# 01_-_CPU.net
KiCad netlist of a schematic drawn in Altium Designer
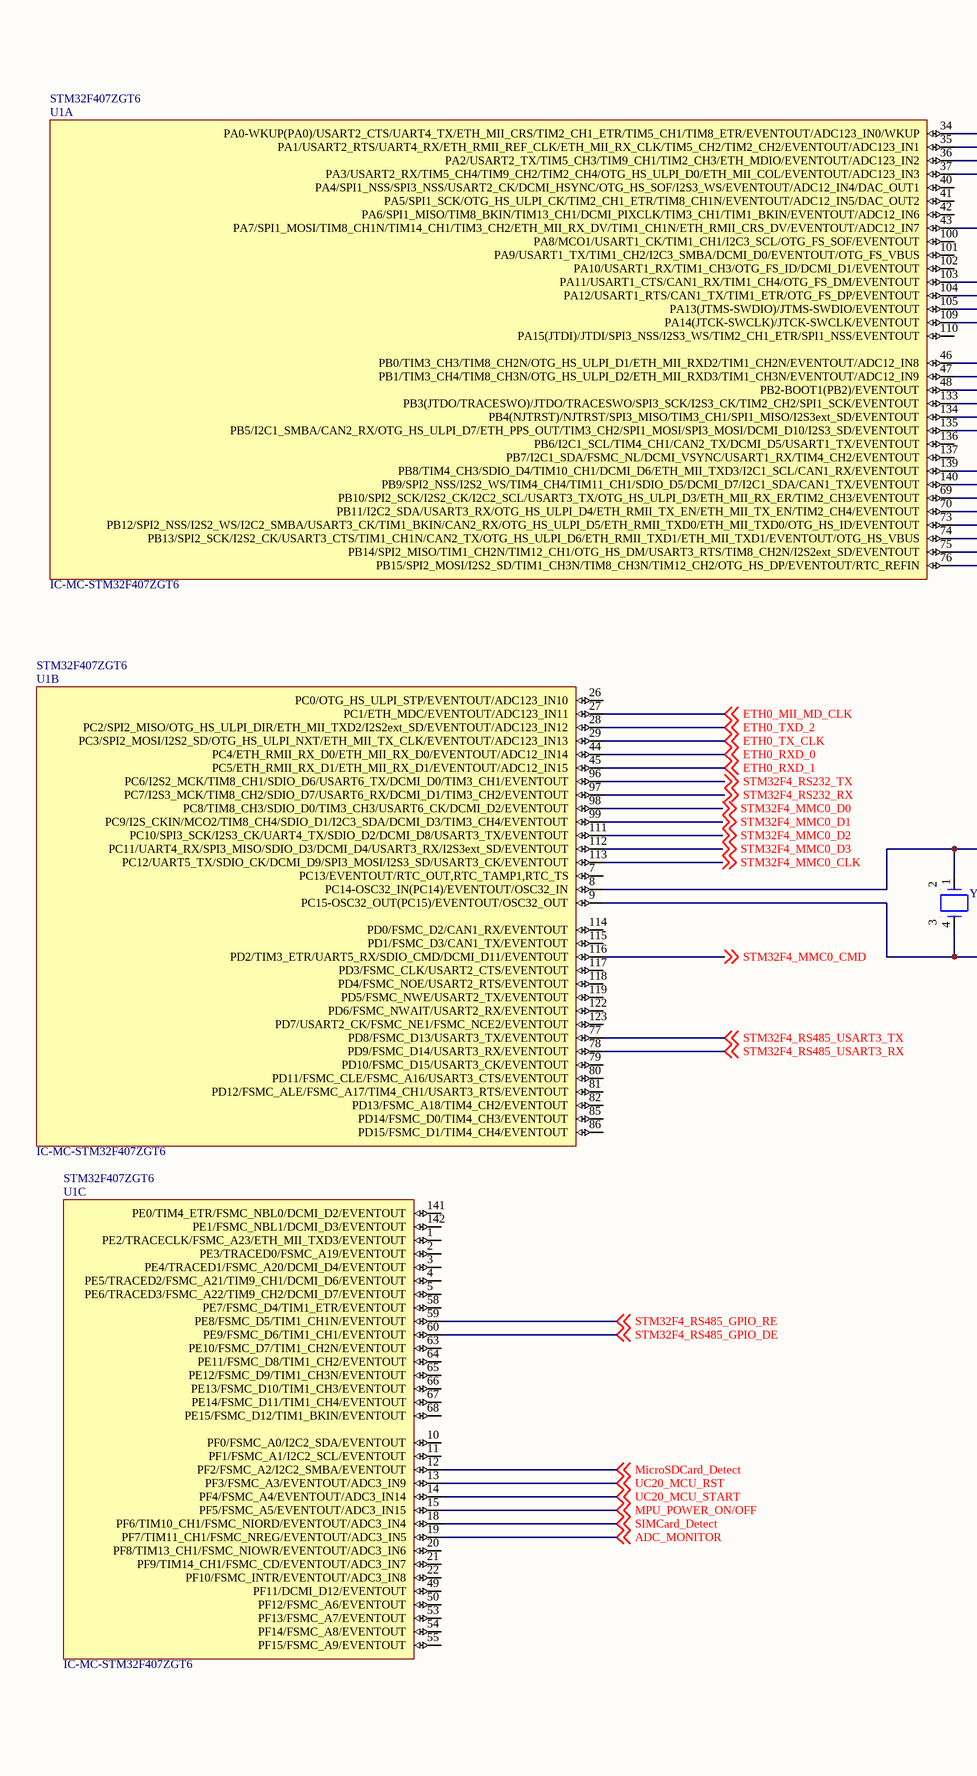
[diagram p0: [01] - CPU.SchDoc, left]
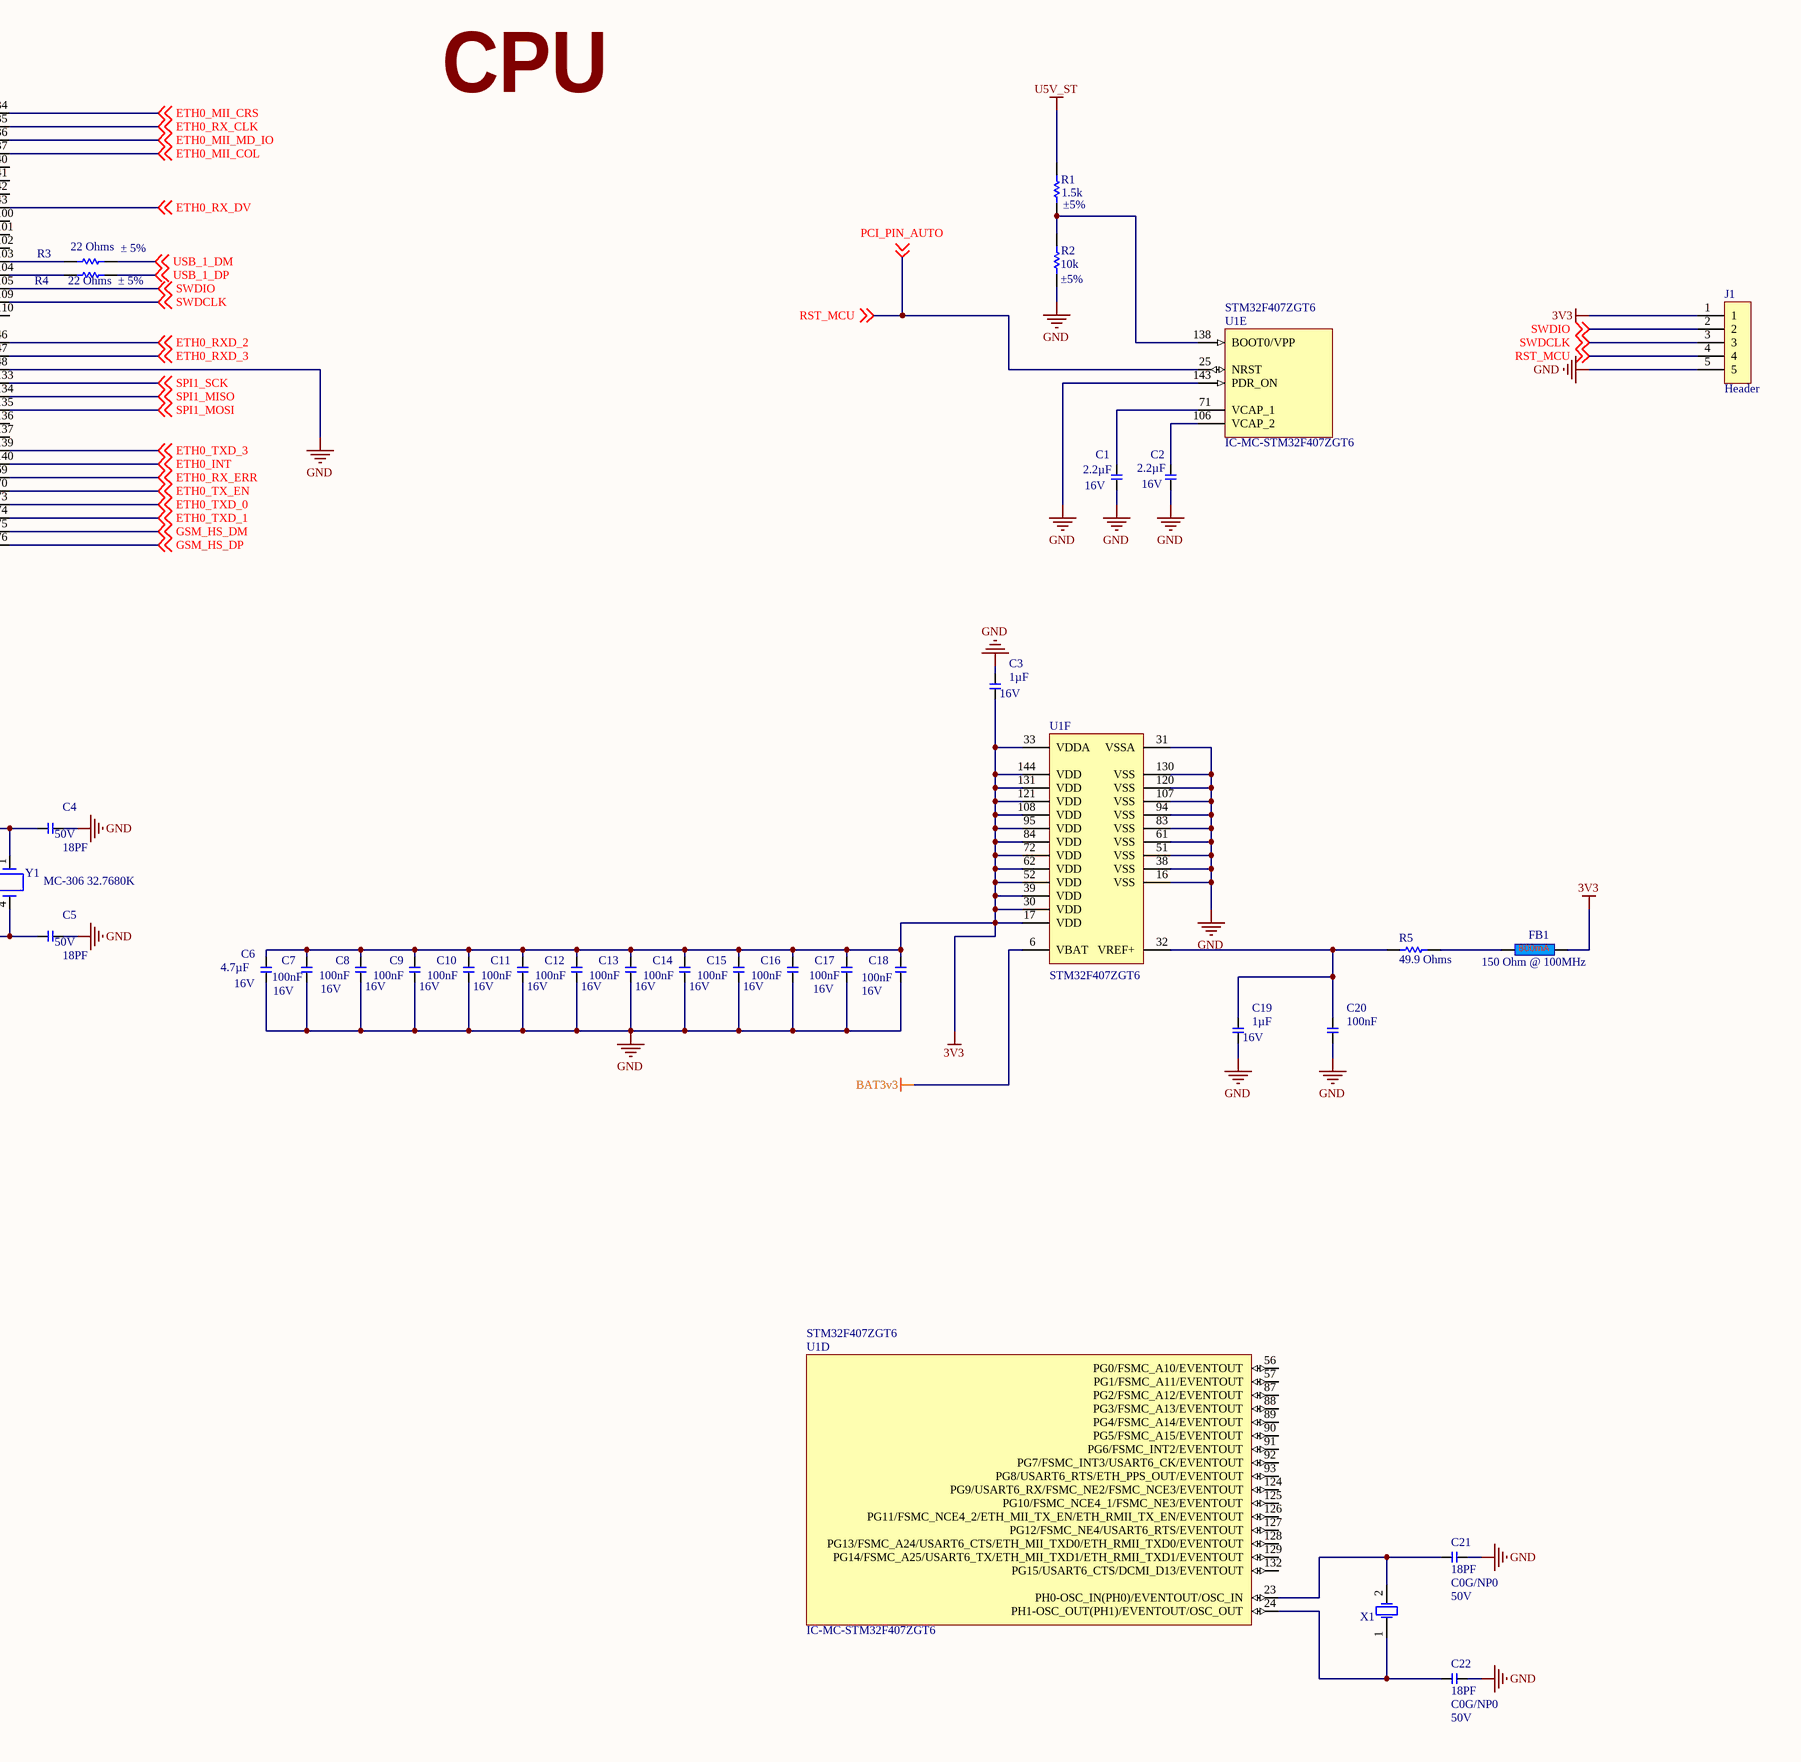
[diagram p1: [01] - CPU.SchDoc, right]

(export (version "E")
  (design (tool "Eeschema 10.0.6"))
  (components
    (comp (ref "C1")
      (value "2.2µF")
      (footprint "C0805")
      (description "KEMET - C0805C225K4RACTU - CAP, MLCC, X7R, 2.2UF, 16V, 0805")
      (fields
        (field (name "MANUFACTURER") "Kemet")
        (field (name "MANUFACTURER PART NUMBER") "C0805C225K4RACTU")
        (field (name "CAPACITANCE") "2.2µF")
        (field (name "VOLTAGE - RATED") "16V")
      )
      (libsource (lib "CPU_STM_080816") (part "C-2.2UF,16V,0805"))
    )
    (comp (ref "C2")
      (value "2.2µF")
      (footprint "C0805")
      (description "KEMET - C0805C225K4RACTU - CAP, MLCC, X7R, 2.2UF, 16V, 0805")
      (fields
        (field (name "MANUFACTURER") "Kemet")
        (field (name "MANUFACTURER PART NUMBER") "C0805C225K4RACTU")
        (field (name "CAPACITANCE") "2.2µF")
        (field (name "VOLTAGE - RATED") "16V")
      )
      (libsource (lib "CPU_STM_080816") (part "C-2.2UF,16V,0805"))
    )
    (comp (ref "C3")
      (value "1µF")
      (footprint "C0805")
      (description "AVX - 0805YC105KAT2A - CAP, MLCC, X7R, 1UF, 16V, 0805")
      (fields
        (field (name "MANUFACTURER") "AVX Corporation")
        (field (name "MANUFACTURER PART NUMBER") "0805YC105KAT2A")
        (field (name "VOLTAGE - RATED") "16V")
      )
      (libsource (lib "CPU_STM_080816") (part "C-1UF,16V,0805"))
    )
    (comp (ref "C4")
      (value "18PF")
      (footprint "C0805")
      (description "MULTICOMP - MC0805N180J500CT - CAP, MLCC, C0G/NP0, 18PF, 50V,0805, REEL")
      (fields
        (field (name "MANUFACTURER") "Multicomp")
        (field (name "MANUFACTURER PART NUMBER") "MC0805N180J500CT")
        (field (name "VOLTAGE_RATING_DC") "50V")
      )
      (libsource (lib "CPU_STM_080816") (part "C-18PF,50V,0805"))
    )
    (comp (ref "C5")
      (value "18PF")
      (footprint "C0805")
      (description "MULTICOMP - MC0805N180J500CT - CAP, MLCC, C0G/NP0, 18PF, 50V,0805, REEL")
      (fields
        (field (name "MANUFACTURER") "Multicomp")
        (field (name "MANUFACTURER PART NUMBER") "MC0805N180J500CT")
        (field (name "VOLTAGE_RATING_DC") "50V")
      )
      (libsource (lib "CPU_STM_080816") (part "C-18PF,50V,0805"))
    )
    (comp (ref "C6")
      (value "4.7µF")
      (footprint "C0805")
      (description "AVX - 0805YC475KAT2A - CAP, MLCC, X7R, 4.7UF, 16V, 0805")
      (fields
        (field (name "MANUFACTURER") "AVX Corporation")
        (field (name "MANUFACTURER PART NUMBER") "0805YC475KAT2A")
        (field (name "VOLTAGE - RATED") "16V")
      )
      (libsource (lib "CPU_STM_080816") (part "C-4.7UF,16V,0805"))
    )
    (comp (ref "C7")
      (value "100nF")
      (footprint "C0805")
      (description "AVX - 0805YA103JAT2A - CAP, MLCC, C0G/NP0, 10NF, 16V, 0805")
      (fields
        (field (name "MANUFACTURER") "AVX")
        (field (name "MANUFACTURER PART NUMBER") "0805YA103JAT2A")
        (field (name "VOLTAGE - RATED") "16V")
      )
      (libsource (lib "CPU_STM_080816") (part "C-100NF,16V,0805"))
    )
    (comp (ref "C8")
      (value "100nF")
      (footprint "C0805")
      (description "AVX - 0805YA103JAT2A - CAP, MLCC, C0G/NP0, 10NF, 16V, 0805")
      (fields
        (field (name "MANUFACTURER") "AVX")
        (field (name "MANUFACTURER PART NUMBER") "0805YA103JAT2A")
        (field (name "VOLTAGE - RATED") "16V")
      )
      (libsource (lib "CPU_STM_080816") (part "C-100NF,16V,0805"))
    )
    (comp (ref "C9")
      (value "100nF")
      (footprint "C0805")
      (description "AVX - 0805YA103JAT2A - CAP, MLCC, C0G/NP0, 10NF, 16V, 0805")
      (fields
        (field (name "MANUFACTURER") "AVX")
        (field (name "MANUFACTURER PART NUMBER") "0805YA103JAT2A")
        (field (name "VOLTAGE - RATED") "16V")
      )
      (libsource (lib "CPU_STM_080816") (part "C-100NF,16V,0805"))
    )
    (comp (ref "C10")
      (value "100nF")
      (footprint "C0805")
      (description "AVX - 0805YA103JAT2A - CAP, MLCC, C0G/NP0, 10NF, 16V, 0805")
      (fields
        (field (name "MANUFACTURER") "AVX")
        (field (name "MANUFACTURER PART NUMBER") "0805YA103JAT2A")
        (field (name "VOLTAGE - RATED") "16V")
      )
      (libsource (lib "CPU_STM_080816") (part "C-100NF,16V,0805"))
    )
    (comp (ref "C11")
      (value "100nF")
      (footprint "C0805")
      (description "AVX - 0805YA103JAT2A - CAP, MLCC, C0G/NP0, 10NF, 16V, 0805")
      (fields
        (field (name "MANUFACTURER") "AVX")
        (field (name "MANUFACTURER PART NUMBER") "0805YA103JAT2A")
        (field (name "VOLTAGE - RATED") "16V")
      )
      (libsource (lib "CPU_STM_080816") (part "C-100NF,16V,0805"))
    )
    (comp (ref "C12")
      (value "100nF")
      (footprint "C0805")
      (description "AVX - 0805YA103JAT2A - CAP, MLCC, C0G/NP0, 10NF, 16V, 0805")
      (fields
        (field (name "MANUFACTURER") "AVX")
        (field (name "MANUFACTURER PART NUMBER") "0805YA103JAT2A")
        (field (name "VOLTAGE - RATED") "16V")
      )
      (libsource (lib "CPU_STM_080816") (part "C-100NF,16V,0805"))
    )
    (comp (ref "C13")
      (value "100nF")
      (footprint "C0805")
      (description "AVX - 0805YA103JAT2A - CAP, MLCC, C0G/NP0, 10NF, 16V, 0805")
      (fields
        (field (name "MANUFACTURER") "AVX")
        (field (name "MANUFACTURER PART NUMBER") "0805YA103JAT2A")
        (field (name "VOLTAGE - RATED") "16V")
      )
      (libsource (lib "CPU_STM_080816") (part "C-100NF,16V,0805"))
    )
    (comp (ref "C14")
      (value "100nF")
      (footprint "C0805")
      (description "AVX - 0805YA103JAT2A - CAP, MLCC, C0G/NP0, 10NF, 16V, 0805")
      (fields
        (field (name "MANUFACTURER") "AVX")
        (field (name "MANUFACTURER PART NUMBER") "0805YA103JAT2A")
        (field (name "VOLTAGE - RATED") "16V")
      )
      (libsource (lib "CPU_STM_080816") (part "C-100NF,16V,0805"))
    )
    (comp (ref "C15")
      (value "100nF")
      (footprint "C0805")
      (description "AVX - 0805YA103JAT2A - CAP, MLCC, C0G/NP0, 10NF, 16V, 0805")
      (fields
        (field (name "MANUFACTURER") "AVX")
        (field (name "MANUFACTURER PART NUMBER") "0805YA103JAT2A")
        (field (name "VOLTAGE - RATED") "16V")
      )
      (libsource (lib "CPU_STM_080816") (part "C-100NF,16V,0805"))
    )
    (comp (ref "C16")
      (value "100nF")
      (footprint "C0805")
      (description "AVX - 0805YA103JAT2A - CAP, MLCC, C0G/NP0, 10NF, 16V, 0805")
      (fields
        (field (name "MANUFACTURER") "AVX")
        (field (name "MANUFACTURER PART NUMBER") "0805YA103JAT2A")
        (field (name "VOLTAGE - RATED") "16V")
      )
      (libsource (lib "CPU_STM_080816") (part "C-100NF,16V,0805"))
    )
    (comp (ref "C17")
      (value "100nF")
      (footprint "C0805")
      (description "AVX - 0805YA103JAT2A - CAP, MLCC, C0G/NP0, 10NF, 16V, 0805")
      (fields
        (field (name "MANUFACTURER") "AVX")
        (field (name "MANUFACTURER PART NUMBER") "0805YA103JAT2A")
        (field (name "VOLTAGE - RATED") "16V")
      )
      (libsource (lib "CPU_STM_080816") (part "C-100NF,16V,0805"))
    )
    (comp (ref "C18")
      (value "100nF")
      (footprint "C0805")
      (description "AVX - 0805YA103JAT2A - CAP, MLCC, C0G/NP0, 10NF, 16V, 0805")
      (fields
        (field (name "MANUFACTURER") "AVX")
        (field (name "MANUFACTURER PART NUMBER") "0805YA103JAT2A")
        (field (name "VOLTAGE - RATED") "16V")
      )
      (libsource (lib "CPU_STM_080816") (part "C-100NF,16V,0805"))
    )
    (comp (ref "C19")
      (value "1µF")
      (footprint "C0805")
      (description "AVX - 0805YC105KAT2A - CAP, MLCC, X7R, 1UF, 16V, 0805")
      (fields
        (field (name "MANUFACTURER") "AVX Corporation")
        (field (name "MANUFACTURER PART NUMBER") "0805YC105KAT2A")
        (field (name "VOLTAGE - RATED") "16V")
      )
      (libsource (lib "CPU_STM_080816") (part "C-1UF,16V,0805"))
    )
    (comp (ref "C20")
      (value "100nF")
      (footprint "C0805")
      (description "AVX - 0805YA103JAT2A - CAP, MLCC, C0G/NP0, 10NF, 16V, 0805")
      (fields (field (name "MANUFACTURER") "AVX") (field (name "MANUFACTURER PART NUMBER") "0805YA103JAT2A"))
      (libsource (lib "CPU_STM_080816") (part "C-100NF,16V,0805"))
    )
    (comp (ref "C21")
      (value "18PF")
      (footprint "C0805")
      (description "MULTICOMP - MC0805N180J500CT - CAP, MLCC, C0G/NP0, 18PF, 50V,0805, REEL")
      (fields
        (field (name "MANUFACTURER") "Multicomp")
        (field (name "MANUFACTURER PART NUMBER") "MC0805N180J500CT")
        (field (name "DIELECTRIC_CHARACTERISTIC") "C0G/NP0")
        (field (name "VOLTAGE_RATING_DC") "50V")
      )
      (libsource (lib "CPU_STM_080816") (part "C-18PF,50V,0805"))
    )
    (comp (ref "C22")
      (value "18PF")
      (footprint "C0805")
      (description "MULTICOMP - MC0805N180J500CT - CAP, MLCC, C0G/NP0, 18PF, 50V,0805, REEL")
      (fields
        (field (name "MANUFACTURER") "Multicomp")
        (field (name "MANUFACTURER PART NUMBER") "MC0805N180J500CT")
        (field (name "DIELECTRIC_CHARACTERISTIC") "C0G/NP0")
        (field (name "VOLTAGE_RATING_DC") "50V")
      )
      (libsource (lib "CPU_STM_080816") (part "C-18PF,50V,0805"))
    )
    (comp (ref "FB1")
      (value "150 Ohm @ 100MHz")
      (footprint "0805")
      (description "FERRITE 800MA 150 OHM 0805 SMD")
      (fields
        (field (name "MANUFACTURER") "Laird-Signal Integrity Products")
        (field (name "MANUFACTURER PART NUMBER") "LI0805H151R-10")
      )
      (libsource (lib "CPU_STM_080816") (part "L-150OHM,800MA"))
    )
    (comp (ref "J1")
      (value "Header")
      (footprint "Header 1x5 2.54mm")
      (description "Header 1X5 2.54")
      (libsource (lib "CPU_STM_080816") (part "CON-Header 1X5 2.54MM"))
    )
    (comp (ref "R1")
      (value "1.5k")
      (footprint "R0805")
      (description "RES SMD 1.5K OHM 1% 1/8W 0805")
      (fields
        (field (name "MANUFACTURER") "Yageo")
        (field (name "MANUFACTURER PART NUMBER") "RC0805FR-071K5L")
        (field (name "TOLERANCE") "±5%")
        (field (name "RESISTANCE (OHMS)") "1.5k")
      )
      (libsource (lib "CPU_STM_080816") (part "R-1.5K,%1,0805"))
    )
    (comp (ref "R2")
      (value "R-10K,%1,0805")
      (footprint "R0805")
      (description "RES SMD 10K OHM 1% 1/8W 0805")
      (fields
        (field (name "MANUFACTURER") "Yageo")
        (field (name "MANUFACTURER PART NUMBER") "RC0805FR-0710KL")
        (field (name "TOLERANCE") "±5%")
        (field (name "RESISTANCE (OHMS)") "10k")
      )
      (libsource (lib "CPU_STM_080816") (part "R-10K,%1,0805"))
    )
    (comp (ref "R3")
      (value "22 Ohms")
      (footprint "R0805")
      (description "PANASONIC - ERJP06F22R0V - RESISTOR, THICK FILM, 22 OHM, 0.5W, 1%")
      (fields
        (field (name "MANUFACTURER") "PANASONIC")
        (field (name "MANUFACTURER PART NUMBER") "ERJP06F22R0V")
        (field (name "RESISTANCE TOLERANCE") "± 5%")
      )
      (libsource (lib "CPU_STM_080816") (part "R-22R,0805"))
    )
    (comp (ref "R4")
      (value "22 Ohms")
      (footprint "R0805")
      (description "PANASONIC - ERJP06F22R0V - RESISTOR, THICK FILM, 22 OHM, 0.5W, 1%")
      (fields
        (field (name "MANUFACTURER") "PANASONIC")
        (field (name "MANUFACTURER PART NUMBER") "ERJP06F22R0V")
        (field (name "RESISTANCE TOLERANCE") "± 5%")
      )
      (libsource (lib "CPU_STM_080816") (part "R-22R,0805"))
    )
    (comp (ref "R5")
      (value "49.9 Ohms")
      (footprint "R0805")
      (description "PANASONIC - ERJP06F49R9V - RESISTOR, THICK FILM, 49.9 OHM, 0.5W, 1%")
      (fields
        (field (name "MANUFACTURER") "PANASONIC")
        (field (name "MANUFACTURER PART NUMBER") "ERJP06F49R9V")
      )
      (libsource (lib "CPU_STM_080816") (part "R-49.9R,0805"))
    )
    (comp (ref "U1")
      (value "IC-MC-STM32F407ZGT6")
      (footprint "STM-LQFP144_L")
      (description "IC MCU 32BIT 1MB FLASH 144LQFP")
      (fields
        (field (name "MANUFACTURER") "STMicroelectronics")
        (field (name "MANUFACTURER PART NUMBER") "STM32F407ZGT6")
      )
      (libsource (lib "CPU_STM_080816") (part "IC-MC-STM32F407ZGT6"))
    )
    (comp (ref "X1")
      (value "ABM7-8.000MHZ")
      (footprint "SM_OSC_ABM3")
      (description "CRYSTAL 8.0000MHZ 18PF SMD")
      (fields
        (field (name "MANUFACTURER") "Abracon LLC")
        (field (name "MANUFACTURER PART NUMBER") "ABM7-8.000MHZ-D2Y-T")
      )
      (libsource (lib "CPU_STM_080816") (part "OSC-ABM7-8.000MHZ-D2Y-T"))
    )
    (comp (ref "Y1")
      (value "32.7680 KHZ 12.5PF")
      (footprint "CRSTAL_RTC")
      (description "CRYSTAL 32.7680 KHZ 12.5PF SMD")
      (fields
        (field (name "MANUFACTURER") "EPSON")
        (field (name "MANUFACTURER PART NUMBER") "MC-306 32.7680K")
      )
      (libsource (lib "CPU_STM_080816") (part "OSC-CRYSTAL 32.7680 KHZ"))
    )
  )
  (nets
    (net (code "1") (name "3V3") (class "Default")
      (node (ref "C10") (pin "2") (pinfunction "2_2") (pintype "passive"))
      (node (ref "C11") (pin "2") (pinfunction "2_2") (pintype "passive"))
      (node (ref "C12") (pin "2") (pinfunction "2_2") (pintype "passive"))
      (node (ref "C13") (pin "2") (pinfunction "2_2") (pintype "passive"))
      (node (ref "C14") (pin "2") (pinfunction "2_2") (pintype "passive"))
      (node (ref "C15") (pin "2") (pinfunction "2_2") (pintype "passive"))
      (node (ref "C16") (pin "2") (pinfunction "2_2") (pintype "passive"))
      (node (ref "C17") (pin "2") (pinfunction "2_2") (pintype "passive"))
      (node (ref "C18") (pin "2") (pinfunction "2_2") (pintype "passive"))
      (node (ref "C3") (pin "1") (pinfunction "1_1") (pintype "passive"))
      (node (ref "C6") (pin "2") (pinfunction "2_2") (pintype "passive"))
      (node (ref "C7") (pin "2") (pinfunction "2_2") (pintype "passive"))
      (node (ref "C8") (pin "2") (pinfunction "2_2") (pintype "passive"))
      (node (ref "C9") (pin "2") (pinfunction "2_2") (pintype "passive"))
      (node (ref "FB1") (pin "2") (pinfunction "2_2") (pintype "passive"))
      (node (ref "J1") (pin "1") (pinfunction "1_1") (pintype "passive"))
      (node (ref "U1") (pin "108") (pinfunction "VDD_108") (pintype "power_in"))
      (node (ref "U1") (pin "121") (pinfunction "VDD_121") (pintype "power_in"))
      (node (ref "U1") (pin "131") (pinfunction "VDD_131") (pintype "power_in"))
      (node (ref "U1") (pin "144") (pinfunction "VDD_144") (pintype "power_in"))
      (node (ref "U1") (pin "17") (pinfunction "VDD_17") (pintype "power_in"))
      (node (ref "U1") (pin "30") (pinfunction "VDD_30") (pintype "power_in"))
      (node (ref "U1") (pin "33") (pinfunction "VDDA_33") (pintype "power_in"))
      (node (ref "U1") (pin "39") (pinfunction "VDD_39") (pintype "power_in"))
      (node (ref "U1") (pin "52") (pinfunction "VDD_52") (pintype "power_in"))
      (node (ref "U1") (pin "62") (pinfunction "VDD_62") (pintype "power_in"))
      (node (ref "U1") (pin "72") (pinfunction "VDD_72") (pintype "power_in"))
      (node (ref "U1") (pin "84") (pinfunction "VDD_84") (pintype "power_in"))
      (node (ref "U1") (pin "95") (pinfunction "VDD_95") (pintype "power_in"))
    )
    (net (code "2") (name "ADC_MONITOR") (class "Default")
      (node (ref "U1") (pin "19") (pinfunction "PF7/TIM11_CH1/FSMC_NREG/EVENTOUT/ADC3_IN5_19") (pintype "bidirectional"))
    )
    (net (code "3") (name "BAT3v3") (class "Default")
      (node (ref "U1") (pin "6") (pinfunction "VBAT_6") (pintype "power_in"))
    )
    (net (code "4") (name "ETH0_INT") (class "Default")
      (node (ref "U1") (pin "140") (pinfunction "PB9/SPI2_NSS/I2S2_WS/TIM4_CH4/TIM11_CH1/SDIO_D5/DCMI_D7/I2C1_SDA/CAN1_TX/EVENTOUT_140") (pintype "bidirectional"))
    )
    (net (code "5") (name "ETH0_MII_COL") (class "Default")
      (node (ref "U1") (pin "37") (pinfunction "PA3/USART2_RX/TIM5_CH4/TIM9_CH2/TIM2_CH4/OTG_HS_ULPI_D0/ETH_MII_COL/EVENTOUT/ADC123_IN3_37") (pintype "bidirectional"))
    )
    (net (code "6") (name "ETH0_MII_CRS") (class "Default")
      (node (ref "U1") (pin "34") (pinfunction "PA0-WKUP(PA0)/USART2_CTS/UART4_TX/ETH_MII_CRS/TIM2_CH1_ETR/TIM5_CH1/TIM8_ETR/EVENTOUT/ADC123_IN0/WKUP_34") (pintype "bidirectional"))
    )
    (net (code "7") (name "ETH0_MII_MD_CLK") (class "Default")
      (node (ref "U1") (pin "27") (pinfunction "PC1/ETH_MDC/EVENTOUT/ADC123_IN11_27") (pintype "bidirectional"))
    )
    (net (code "8") (name "ETH0_MII_MD_IO") (class "Default")
      (node (ref "U1") (pin "36") (pinfunction "PA2/USART2_TX/TIM5_CH3/TIM9_CH1/TIM2_CH3/ETH_MDIO/EVENTOUT/ADC123_IN2_36") (pintype "bidirectional"))
    )
    (net (code "9") (name "ETH0_RXD_0") (class "Default")
      (node (ref "U1") (pin "44") (pinfunction "PC4/ETH_RMII_RX_D0/ETH_MII_RX_D0/EVENTOUT/ADC12_IN14_44") (pintype "bidirectional"))
    )
    (net (code "10") (name "ETH0_RXD_1") (class "Default")
      (node (ref "U1") (pin "45") (pinfunction "PC5/ETH_RMII_RX_D1/ETH_MII_RX_D1/EVENTOUT/ADC12_IN15_45") (pintype "bidirectional"))
    )
    (net (code "11") (name "ETH0_RXD_2") (class "Default")
      (node (ref "U1") (pin "46") (pinfunction "PB0/TIM3_CH3/TIM8_CH2N/OTG_HS_ULPI_D1/ETH_MII_RXD2/TIM1_CH2N/EVENTOUT/ADC12_IN8_46") (pintype "bidirectional"))
    )
    (net (code "12") (name "ETH0_RXD_3") (class "Default")
      (node (ref "U1") (pin "47") (pinfunction "PB1/TIM3_CH4/TIM8_CH3N/OTG_HS_ULPI_D2/ETH_MII_RXD3/TIM1_CH3N/EVENTOUT/ADC12_IN9_47") (pintype "bidirectional"))
    )
    (net (code "13") (name "ETH0_RX_CLK") (class "Default")
      (node (ref "U1") (pin "35") (pinfunction "PA1/USART2_RTS/UART4_RX/ETH_RMII_REF_CLK/ETH_MII_RX_CLK/TIM5_CH2/TIM2_CH2/EVENTOUT/ADC123_IN1_35") (pintype "bidirectional"))
    )
    (net (code "14") (name "ETH0_RX_DV") (class "Default")
      (node (ref "U1") (pin "43") (pinfunction "PA7/SPI1_MOSI/TIM8_CH1N/TIM14_CH1/TIM3_CH2/ETH_MII_RX_DV/TIM1_CH1N/ETH_RMII_CRS_DV/EVENTOUT/ADC12_IN7_43") (pintype "bidirectional"))
    )
    (net (code "15") (name "ETH0_RX_ERR") (class "Default")
      (node (ref "U1") (pin "69") (pinfunction "PB10/SPI2_SCK/I2S2_CK/I2C2_SCL/USART3_TX/OTG_HS_ULPI_D3/ETH_MII_RX_ER/TIM2_CH3/EVENTOUT_69") (pintype "bidirectional"))
    )
    (net (code "16") (name "ETH0_TXD_0") (class "Default")
      (node (ref "U1") (pin "73") (pinfunction "PB12/SPI2_NSS/I2S2_WS/I2C2_SMBA/USART3_CK/TIM1_BKIN/CAN2_RX/OTG_HS_ULPI_D5/ETH_RMII_TXD0/ETH_MII_TXD0/OTG_HS_ID/EVENTOUT_73") (pintype "bidirectional"))
    )
    (net (code "17") (name "ETH0_TXD_1") (class "Default")
      (node (ref "U1") (pin "74") (pinfunction "PB13/SPI2_SCK/I2S2_CK/USART3_CTS/TIM1_CH1N/CAN2_TX/OTG_HS_ULPI_D6/ETH_RMII_TXD1/ETH_MII_TXD1/EVENTOUT/OTG_HS_VBUS_74") (pintype "bidirectional"))
    )
    (net (code "18") (name "ETH0_TXD_2") (class "Default")
      (node (ref "U1") (pin "28") (pinfunction "PC2/SPI2_MISO/OTG_HS_ULPI_DIR/ETH_MII_TXD2/I2S2ext_SD/EVENTOUT/ADC123_IN12_28") (pintype "bidirectional"))
    )
    (net (code "19") (name "ETH0_TXD_3") (class "Default")
      (node (ref "U1") (pin "139") (pinfunction "PB8/TIM4_CH3/SDIO_D4/TIM10_CH1/DCMI_D6/ETH_MII_TXD3/I2C1_SCL/CAN1_RX/EVENTOUT_139") (pintype "bidirectional"))
    )
    (net (code "20") (name "ETH0_TX_CLK") (class "Default")
      (node (ref "U1") (pin "29") (pinfunction "PC3/SPI2_MOSI/I2S2_SD/OTG_HS_ULPI_NXT/ETH_MII_TX_CLK/EVENTOUT/ADC123_IN13_29") (pintype "bidirectional"))
    )
    (net (code "21") (name "ETH0_TX_EN") (class "Default")
      (node (ref "U1") (pin "70") (pinfunction "PB11/I2C2_SDA/USART3_RX/OTG_HS_ULPI_D4/ETH_RMII_TX_EN/ETH_MII_TX_EN/TIM2_CH4/EVENTOUT_70") (pintype "bidirectional"))
    )
    (net (code "22") (name "GND") (class "Default")
      (node (ref "C1") (pin "1") (pinfunction "1_1") (pintype "passive"))
      (node (ref "C10") (pin "1") (pinfunction "1_1") (pintype "passive"))
      (node (ref "C11") (pin "1") (pinfunction "1_1") (pintype "passive"))
      (node (ref "C12") (pin "1") (pinfunction "1_1") (pintype "passive"))
      (node (ref "C13") (pin "1") (pinfunction "1_1") (pintype "passive"))
      (node (ref "C14") (pin "1") (pinfunction "1_1") (pintype "passive"))
      (node (ref "C15") (pin "1") (pinfunction "1_1") (pintype "passive"))
      (node (ref "C16") (pin "1") (pinfunction "1_1") (pintype "passive"))
      (node (ref "C17") (pin "1") (pinfunction "1_1") (pintype "passive"))
      (node (ref "C18") (pin "1") (pinfunction "1_1") (pintype "passive"))
      (node (ref "C19") (pin "1") (pinfunction "1_1") (pintype "passive"))
      (node (ref "C2") (pin "1") (pinfunction "1_1") (pintype "passive"))
      (node (ref "C20") (pin "1") (pinfunction "1_1") (pintype "passive"))
      (node (ref "C21") (pin "2") (pinfunction "2_2") (pintype "passive"))
      (node (ref "C22") (pin "2") (pinfunction "2_2") (pintype "passive"))
      (node (ref "C3") (pin "2") (pinfunction "2_2") (pintype "passive"))
      (node (ref "C4") (pin "2") (pinfunction "2_2") (pintype "passive"))
      (node (ref "C5") (pin "2") (pinfunction "2_2") (pintype "passive"))
      (node (ref "C6") (pin "1") (pinfunction "1_1") (pintype "passive"))
      (node (ref "C7") (pin "1") (pinfunction "1_1") (pintype "passive"))
      (node (ref "C8") (pin "1") (pinfunction "1_1") (pintype "passive"))
      (node (ref "C9") (pin "1") (pinfunction "1_1") (pintype "passive"))
      (node (ref "J1") (pin "5") (pinfunction "5_5") (pintype "passive"))
      (node (ref "R2") (pin "1") (pinfunction "1_1") (pintype "passive"))
      (node (ref "U1") (pin "107") (pinfunction "VSS_107") (pintype "power_in"))
      (node (ref "U1") (pin "120") (pinfunction "VSS_120") (pintype "power_in"))
      (node (ref "U1") (pin "130") (pinfunction "VSS_130") (pintype "power_in"))
      (node (ref "U1") (pin "143") (pinfunction "PDR_ON_143") (pintype "input"))
      (node (ref "U1") (pin "16") (pinfunction "VSS_16") (pintype "power_in"))
      (node (ref "U1") (pin "31") (pinfunction "VSSA_31") (pintype "power_in"))
      (node (ref "U1") (pin "38") (pinfunction "VSS_38") (pintype "power_in"))
      (node (ref "U1") (pin "48") (pinfunction "PB2-BOOT1(PB2)/EVENTOUT_48") (pintype "bidirectional"))
      (node (ref "U1") (pin "51") (pinfunction "VSS_51") (pintype "power_in"))
      (node (ref "U1") (pin "61") (pinfunction "VSS_61") (pintype "power_in"))
      (node (ref "U1") (pin "83") (pinfunction "VSS_83") (pintype "power_in"))
      (node (ref "U1") (pin "94") (pinfunction "VSS_94") (pintype "power_in"))
    )
    (net (code "23") (name "GSM_HS_DM") (class "Default")
      (node (ref "U1") (pin "75") (pinfunction "PB14/SPI2_MISO/TIM1_CH2N/TIM12_CH1/OTG_HS_DM/USART3_RTS/TIM8_CH2N/I2S2ext_SD/EVENTOUT_75") (pintype "bidirectional"))
    )
    (net (code "24") (name "GSM_HS_DP") (class "Default")
      (node (ref "U1") (pin "76") (pinfunction "PB15/SPI2_MOSI/I2S2_SD/TIM1_CH3N/TIM8_CH3N/TIM12_CH2/OTG_HS_DP/EVENTOUT/RTC_REFIN_76") (pintype "bidirectional"))
    )
    (net (code "25") (name "MPU_POWER_ON{slash}OFF") (class "Default")
      (node (ref "U1") (pin "15") (pinfunction "PF5/FSMC_A5/EVENTOUT/ADC3_IN15_15") (pintype "bidirectional"))
    )
    (net (code "26") (name "MicroSDCard_Detect") (class "Default")
      (node (ref "U1") (pin "12") (pinfunction "PF2/FSMC_A2/I2C2_SMBA/EVENTOUT_12") (pintype "bidirectional"))
    )
    (net (code "27") (name "Net-(FB1-Pad1)") (class "Default")
      (node (ref "FB1") (pin "1") (pinfunction "1_1") (pintype "passive"))
      (node (ref "R5") (pin "2") (pinfunction "2_2") (pintype "passive"))
    )
    (net (code "28") (name "Net-(U1A-PA11{slash}USART1_CTS{slash}CAN1_RX{slash}TIM1_CH4{slash}OTG_FS_DM{slash}EVENTOUT)") (class "Default")
      (node (ref "R3") (pin "1") (pinfunction "1_1") (pintype "passive"))
      (node (ref "U1") (pin "103") (pinfunction "PA11/USART1_CTS/CAN1_RX/TIM1_CH4/OTG_FS_DM/EVENTOUT_103") (pintype "bidirectional"))
    )
    (net (code "29") (name "Net-(U1A-PA12{slash}USART1_RTS{slash}CAN1_TX{slash}TIM1_ETR{slash}OTG_FS_DP{slash}EVENTOUT)") (class "Default")
      (node (ref "R4") (pin "1") (pinfunction "1_1") (pintype "passive"))
      (node (ref "U1") (pin "104") (pinfunction "PA12/USART1_RTS/CAN1_TX/TIM1_ETR/OTG_FS_DP/EVENTOUT_104") (pintype "bidirectional"))
    )
    (net (code "30") (name "Net-(U1B-PC14-OSC32_IN(PC14){slash}EVENTOUT{slash}OSC32_IN)") (class "Default")
      (node (ref "C4") (pin "1") (pinfunction "1_1") (pintype "passive"))
      (node (ref "U1") (pin "8") (pinfunction "PC14-OSC32_IN(PC14)/EVENTOUT/OSC32_IN_8") (pintype "bidirectional"))
      (node (ref "Y1") (pin "1") (pinfunction "1_1") (pintype "passive"))
    )
    (net (code "31") (name "Net-(U1B-PC15-OSC32_OUT(PC15){slash}EVENTOUT{slash}OSC32_OUT)") (class "Default")
      (node (ref "C5") (pin "1") (pinfunction "1_1") (pintype "passive"))
      (node (ref "U1") (pin "9") (pinfunction "PC15-OSC32_OUT(PC15)/EVENTOUT/OSC32_OUT_9") (pintype "bidirectional"))
      (node (ref "Y1") (pin "4") (pinfunction "4_4") (pintype "passive"))
    )
    (net (code "32") (name "Net-(U1D-PH0-OSC_IN(PH0){slash}EVENTOUT{slash}OSC_IN)") (class "Default")
      (node (ref "C21") (pin "1") (pinfunction "1_1") (pintype "passive"))
      (node (ref "U1") (pin "23") (pinfunction "PH0-OSC_IN(PH0)/EVENTOUT/OSC_IN_23") (pintype "bidirectional"))
      (node (ref "X1") (pin "2") (pinfunction "OSC2_2") (pintype "passive"))
    )
    (net (code "33") (name "Net-(U1D-PH1-OSC_OUT(PH1){slash}EVENTOUT{slash}OSC_OUT)") (class "Default")
      (node (ref "C22") (pin "1") (pinfunction "1_1") (pintype "passive"))
      (node (ref "U1") (pin "24") (pinfunction "PH1-OSC_OUT(PH1)/EVENTOUT/OSC_OUT_24") (pintype "bidirectional"))
      (node (ref "X1") (pin "1") (pinfunction "OSC1_1") (pintype "passive"))
    )
    (net (code "34") (name "Net-(U1E-BOOT0{slash}VPP)") (class "Default")
      (node (ref "R1") (pin "2") (pinfunction "2_2") (pintype "passive"))
      (node (ref "R2") (pin "2") (pinfunction "2_2") (pintype "passive"))
      (node (ref "U1") (pin "138") (pinfunction "BOOT0/VPP_138") (pintype "input"))
    )
    (net (code "35") (name "Net-(U1E-VCAP_1)") (class "Default")
      (node (ref "C1") (pin "2") (pinfunction "2_2") (pintype "passive"))
      (node (ref "U1") (pin "71") (pinfunction "VCAP_1_71") (pintype "power_in"))
    )
    (net (code "36") (name "Net-(U1E-VCAP_2)") (class "Default")
      (node (ref "C2") (pin "2") (pinfunction "2_2") (pintype "passive"))
      (node (ref "U1") (pin "106") (pinfunction "VCAP_2_106") (pintype "power_in"))
    )
    (net (code "37") (name "Net-(U1F-VREF+)") (class "Default")
      (node (ref "C19") (pin "2") (pinfunction "2_2") (pintype "passive"))
      (node (ref "C20") (pin "2") (pinfunction "2_2") (pintype "passive"))
      (node (ref "R5") (pin "1") (pinfunction "1_1") (pintype "passive"))
      (node (ref "U1") (pin "32") (pinfunction "VREF+_32") (pintype "power_in"))
    )
    (net (code "38") (name "PCI_PIN_AUTO") (class "Default")
      (node (ref "J1") (pin "4") (pinfunction "4_4") (pintype "passive"))
      (node (ref "U1") (pin "25") (pinfunction "NRST_25") (pintype "bidirectional"))
    )
    (net (code "39") (name "SIMCard_Detect") (class "Default")
      (node (ref "U1") (pin "18") (pinfunction "PF6/TIM10_CH1/FSMC_NIORD/EVENTOUT/ADC3_IN4_18") (pintype "bidirectional"))
    )
    (net (code "40") (name "SPI1_MISO") (class "Default")
      (node (ref "U1") (pin "134") (pinfunction "PB4(NJTRST)/NJTRST/SPI3_MISO/TIM3_CH1/SPI1_MISO/I2S3ext_SD/EVENTOUT_134") (pintype "bidirectional"))
    )
    (net (code "41") (name "SPI1_MOSI") (class "Default")
      (node (ref "U1") (pin "135") (pinfunction "PB5/I2C1_SMBA/CAN2_RX/OTG_HS_ULPI_D7/ETH_PPS_OUT/TIM3_CH2/SPI1_MOSI/SPI3_MOSI/DCMI_D10/I2S3_SD/EVENTOUT_135") (pintype "bidirectional"))
    )
    (net (code "42") (name "SPI1_SCK") (class "Default")
      (node (ref "U1") (pin "133") (pinfunction "PB3(JTDO/TRACESWO)/JTDO/TRACESWO/SPI3_SCK/I2S3_CK/TIM2_CH2/SPI1_SCK/EVENTOUT_133") (pintype "bidirectional"))
    )
    (net (code "43") (name "STM32F4_MMC0_CLK") (class "Default")
      (node (ref "U1") (pin "113") (pinfunction "PC12/UART5_TX/SDIO_CK/DCMI_D9/SPI3_MOSI/I2S3_SD/USART3_CK/EVENTOUT_113") (pintype "bidirectional"))
    )
    (net (code "44") (name "STM32F4_MMC0_CMD") (class "Default")
      (node (ref "U1") (pin "116") (pinfunction "PD2/TIM3_ETR/UART5_RX/SDIO_CMD/DCMI_D11/EVENTOUT_116") (pintype "bidirectional"))
    )
    (net (code "45") (name "STM32F4_MMC0_D0") (class "Default")
      (node (ref "U1") (pin "98") (pinfunction "PC8/TIM8_CH3/SDIO_D0/TIM3_CH3/USART6_CK/DCMI_D2/EVENTOUT_98") (pintype "bidirectional"))
    )
    (net (code "46") (name "STM32F4_MMC0_D1") (class "Default")
      (node (ref "U1") (pin "99") (pinfunction "PC9/I2S_CKIN/MCO2/TIM8_CH4/SDIO_D1/I2C3_SDA/DCMI_D3/TIM3_CH4/EVENTOUT_99") (pintype "bidirectional"))
    )
    (net (code "47") (name "STM32F4_MMC0_D2") (class "Default")
      (node (ref "U1") (pin "111") (pinfunction "PC10/SPI3_SCK/I2S3_CK/UART4_TX/SDIO_D2/DCMI_D8/USART3_TX/EVENTOUT_111") (pintype "bidirectional"))
    )
    (net (code "48") (name "STM32F4_MMC0_D3") (class "Default")
      (node (ref "U1") (pin "112") (pinfunction "PC11/UART4_RX/SPI3_MISO/SDIO_D3/DCMI_D4/USART3_RX/I2S3ext_SD/EVENTOUT_112") (pintype "bidirectional"))
    )
    (net (code "49") (name "STM32F4_RS232_RX") (class "Default")
      (node (ref "U1") (pin "97") (pinfunction "PC7/I2S3_MCK/TIM8_CH2/SDIO_D7/USART6_RX/DCMI_D1/TIM3_CH2/EVENTOUT_97") (pintype "bidirectional"))
    )
    (net (code "50") (name "STM32F4_RS232_TX") (class "Default")
      (node (ref "U1") (pin "96") (pinfunction "PC6/I2S2_MCK/TIM8_CH1/SDIO_D6/USART6_TX/DCMI_D0/TIM3_CH1/EVENTOUT_96") (pintype "bidirectional"))
    )
    (net (code "51") (name "STM32F4_RS485_GPIO_DE") (class "Default")
      (node (ref "U1") (pin "60") (pinfunction "PE9/FSMC_D6/TIM1_CH1/EVENTOUT_60") (pintype "bidirectional"))
    )
    (net (code "52") (name "STM32F4_RS485_GPIO_RE") (class "Default")
      (node (ref "U1") (pin "59") (pinfunction "PE8/FSMC_D5/TIM1_CH1N/EVENTOUT_59") (pintype "bidirectional"))
    )
    (net (code "53") (name "STM32F4_RS485_USART3_RX") (class "Default")
      (node (ref "U1") (pin "78") (pinfunction "PD9/FSMC_D14/USART3_RX/EVENTOUT_78") (pintype "bidirectional"))
    )
    (net (code "54") (name "STM32F4_RS485_USART3_TX") (class "Default")
      (node (ref "U1") (pin "77") (pinfunction "PD8/FSMC_D13/USART3_TX/EVENTOUT_77") (pintype "bidirectional"))
    )
    (net (code "55") (name "SWDCLK") (class "Default")
      (node (ref "J1") (pin "3") (pinfunction "3_3") (pintype "passive"))
      (node (ref "U1") (pin "109") (pinfunction "PA14(JTCK-SWCLK)/JTCK-SWCLK/EVENTOUT_109") (pintype "bidirectional"))
    )
    (net (code "56") (name "SWDIO") (class "Default")
      (node (ref "J1") (pin "2") (pinfunction "2_2") (pintype "passive"))
      (node (ref "U1") (pin "105") (pinfunction "PA13(JTMS-SWDIO)/JTMS-SWDIO/EVENTOUT_105") (pintype "bidirectional"))
    )
    (net (code "57") (name "U5V_ST") (class "Default")
      (node (ref "R1") (pin "1") (pinfunction "1_1") (pintype "passive"))
    )
    (net (code "58") (name "UC20_MCU_RST") (class "Default")
      (node (ref "U1") (pin "13") (pinfunction "PF3/FSMC_A3/EVENTOUT/ADC3_IN9_13") (pintype "bidirectional"))
    )
    (net (code "59") (name "UC20_MCU_START") (class "Default")
      (node (ref "U1") (pin "14") (pinfunction "PF4/FSMC_A4/EVENTOUT/ADC3_IN14_14") (pintype "bidirectional"))
    )
    (net (code "60") (name "USB_1_DM") (class "Default")
      (node (ref "R3") (pin "2") (pinfunction "2_2") (pintype "passive"))
    )
    (net (code "61") (name "USB_1_DP") (class "Default")
      (node (ref "R4") (pin "2") (pinfunction "2_2") (pintype "passive"))
    )
    (net (code "62") (name "unconnected-(U1A-PA4{slash}SPI1_NSS{slash}SPI3_NSS{slash}USART2_CK{slash}DCMI_HSYNC{slash}OTG_HS_SOF{slash}I2S3_WS{slash}EVENTOUT{slash}ADC12_IN4{slash}DAC_OUT1-Pad40)") (class "Default")
      (node (ref "U1") (pin "40") (pinfunction "PA4/SPI1_NSS/SPI3_NSS/USART2_CK/DCMI_HSYNC/OTG_HS_SOF/I2S3_WS/EVENTOUT/ADC12_IN4/DAC_OUT1_40") (pintype "bidirectional"))
    )
    (net (code "63") (name "unconnected-(U1A-PA5{slash}SPI1_SCK{slash}OTG_HS_ULPI_CK{slash}TIM2_CH1_ETR{slash}TIM8_CH1N{slash}EVENTOUT{slash}ADC12_IN5{slash}DAC_OUT2-Pad41)") (class "Default")
      (node (ref "U1") (pin "41") (pinfunction "PA5/SPI1_SCK/OTG_HS_ULPI_CK/TIM2_CH1_ETR/TIM8_CH1N/EVENTOUT/ADC12_IN5/DAC_OUT2_41") (pintype "bidirectional"))
    )
    (net (code "64") (name "unconnected-(U1A-PA6{slash}SPI1_MISO{slash}TIM8_BKIN{slash}TIM13_CH1{slash}DCMI_PIXCLK{slash}TIM3_CH1{slash}TIM1_BKIN{slash}EVENTOUT{slash}ADC12_IN6-Pad42)") (class "Default")
      (node (ref "U1") (pin "42") (pinfunction "PA6/SPI1_MISO/TIM8_BKIN/TIM13_CH1/DCMI_PIXCLK/TIM3_CH1/TIM1_BKIN/EVENTOUT/ADC12_IN6_42") (pintype "bidirectional"))
    )
    (net (code "65") (name "unconnected-(U1A-PA8{slash}MCO1{slash}USART1_CK{slash}TIM1_CH1{slash}I2C3_SCL{slash}OTG_FS_SOF{slash}EVENTOUT-Pad100)") (class "Default")
      (node (ref "U1") (pin "100") (pinfunction "PA8/MCO1/USART1_CK/TIM1_CH1/I2C3_SCL/OTG_FS_SOF/EVENTOUT_100") (pintype "bidirectional"))
    )
    (net (code "66") (name "unconnected-(U1A-PA9{slash}USART1_TX{slash}TIM1_CH2{slash}I2C3_SMBA{slash}DCMI_D0{slash}EVENTOUT{slash}OTG_FS_VBUS-Pad101)") (class "Default")
      (node (ref "U1") (pin "101") (pinfunction "PA9/USART1_TX/TIM1_CH2/I2C3_SMBA/DCMI_D0/EVENTOUT/OTG_FS_VBUS_101") (pintype "bidirectional"))
    )
    (net (code "67") (name "unconnected-(U1A-PA10{slash}USART1_RX{slash}TIM1_CH3{slash}OTG_FS_ID{slash}DCMI_D1{slash}EVENTOUT-Pad102)") (class "Default")
      (node (ref "U1") (pin "102") (pinfunction "PA10/USART1_RX/TIM1_CH3/OTG_FS_ID/DCMI_D1/EVENTOUT_102") (pintype "bidirectional"))
    )
    (net (code "68") (name "unconnected-(U1A-PA15(JTDI){slash}JTDI{slash}SPI3_NSS{slash}I2S3_WS{slash}TIM2_CH1_ETR{slash}SPI1_NSS{slash}EVENTOUT-Pad110)") (class "Default")
      (node (ref "U1") (pin "110") (pinfunction "PA15(JTDI)/JTDI/SPI3_NSS/I2S3_WS/TIM2_CH1_ETR/SPI1_NSS/EVENTOUT_110") (pintype "bidirectional"))
    )
    (net (code "69") (name "unconnected-(U1A-PB6{slash}I2C1_SCL{slash}TIM4_CH1{slash}CAN2_TX{slash}DCMI_D5{slash}USART1_TX{slash}EVENTOUT-Pad136)") (class "Default")
      (node (ref "U1") (pin "136") (pinfunction "PB6/I2C1_SCL/TIM4_CH1/CAN2_TX/DCMI_D5/USART1_TX/EVENTOUT_136") (pintype "bidirectional"))
    )
    (net (code "70") (name "unconnected-(U1A-PB7{slash}I2C1_SDA{slash}FSMC_NL{slash}DCMI_VSYNC{slash}USART1_RX{slash}TIM4_CH2{slash}EVENTOUT-Pad137)") (class "Default")
      (node (ref "U1") (pin "137") (pinfunction "PB7/I2C1_SDA/FSMC_NL/DCMI_VSYNC/USART1_RX/TIM4_CH2/EVENTOUT_137") (pintype "bidirectional"))
    )
    (net (code "71") (name "unconnected-(U1B-PC0{slash}OTG_HS_ULPI_STP{slash}EVENTOUT{slash}ADC123_IN10-Pad26)") (class "Default")
      (node (ref "U1") (pin "26") (pinfunction "PC0/OTG_HS_ULPI_STP/EVENTOUT/ADC123_IN10_26") (pintype "bidirectional"))
    )
    (net (code "72") (name "unconnected-(U1B-PC13{slash}EVENTOUT{slash}RTC_OUT,RTC_TAMP1,RTC_TS-Pad7)") (class "Default")
      (node (ref "U1") (pin "7") (pinfunction "PC13/EVENTOUT/RTC_OUT,RTC_TAMP1,RTC_TS_7") (pintype "bidirectional"))
    )
    (net (code "73") (name "unconnected-(U1B-PD0{slash}FSMC_D2{slash}CAN1_RX{slash}EVENTOUT-Pad114)") (class "Default")
      (node (ref "U1") (pin "114") (pinfunction "PD0/FSMC_D2/CAN1_RX/EVENTOUT_114") (pintype "bidirectional"))
    )
    (net (code "74") (name "unconnected-(U1B-PD1{slash}FSMC_D3{slash}CAN1_TX{slash}EVENTOUT-Pad115)") (class "Default")
      (node (ref "U1") (pin "115") (pinfunction "PD1/FSMC_D3/CAN1_TX/EVENTOUT_115") (pintype "bidirectional"))
    )
    (net (code "75") (name "unconnected-(U1B-PD3{slash}FSMC_CLK{slash}USART2_CTS{slash}EVENTOUT-Pad117)") (class "Default")
      (node (ref "U1") (pin "117") (pinfunction "PD3/FSMC_CLK/USART2_CTS/EVENTOUT_117") (pintype "bidirectional"))
    )
    (net (code "76") (name "unconnected-(U1B-PD4{slash}FSMC_NOE{slash}USART2_RTS{slash}EVENTOUT-Pad118)") (class "Default")
      (node (ref "U1") (pin "118") (pinfunction "PD4/FSMC_NOE/USART2_RTS/EVENTOUT_118") (pintype "bidirectional"))
    )
    (net (code "77") (name "unconnected-(U1B-PD5{slash}FSMC_NWE{slash}USART2_TX{slash}EVENTOUT-Pad119)") (class "Default")
      (node (ref "U1") (pin "119") (pinfunction "PD5/FSMC_NWE/USART2_TX/EVENTOUT_119") (pintype "bidirectional"))
    )
    (net (code "78") (name "unconnected-(U1B-PD6{slash}FSMC_NWAIT{slash}USART2_RX{slash}EVENTOUT-Pad122)") (class "Default")
      (node (ref "U1") (pin "122") (pinfunction "PD6/FSMC_NWAIT/USART2_RX/EVENTOUT_122") (pintype "bidirectional"))
    )
    (net (code "79") (name "unconnected-(U1B-PD7{slash}USART2_CK{slash}FSMC_NE1{slash}FSMC_NCE2{slash}EVENTOUT-Pad123)") (class "Default")
      (node (ref "U1") (pin "123") (pinfunction "PD7/USART2_CK/FSMC_NE1/FSMC_NCE2/EVENTOUT_123") (pintype "bidirectional"))
    )
    (net (code "80") (name "unconnected-(U1B-PD10{slash}FSMC_D15{slash}USART3_CK{slash}EVENTOUT-Pad79)") (class "Default")
      (node (ref "U1") (pin "79") (pinfunction "PD10/FSMC_D15/USART3_CK/EVENTOUT_79") (pintype "bidirectional"))
    )
    (net (code "81") (name "unconnected-(U1B-PD11{slash}FSMC_CLE{slash}FSMC_A16{slash}USART3_CTS{slash}EVENTOUT-Pad80)") (class "Default")
      (node (ref "U1") (pin "80") (pinfunction "PD11/FSMC_CLE/FSMC_A16/USART3_CTS/EVENTOUT_80") (pintype "bidirectional"))
    )
    (net (code "82") (name "unconnected-(U1B-PD12{slash}FSMC_ALE{slash}FSMC_A17{slash}TIM4_CH1{slash}USART3_RTS{slash}EVENTOUT-Pad81)") (class "Default")
      (node (ref "U1") (pin "81") (pinfunction "PD12/FSMC_ALE/FSMC_A17/TIM4_CH1/USART3_RTS/EVENTOUT_81") (pintype "bidirectional"))
    )
    (net (code "83") (name "unconnected-(U1B-PD13{slash}FSMC_A18{slash}TIM4_CH2{slash}EVENTOUT-Pad82)") (class "Default")
      (node (ref "U1") (pin "82") (pinfunction "PD13/FSMC_A18/TIM4_CH2/EVENTOUT_82") (pintype "bidirectional"))
    )
    (net (code "84") (name "unconnected-(U1B-PD14{slash}FSMC_D0{slash}TIM4_CH3{slash}EVENTOUT-Pad85)") (class "Default")
      (node (ref "U1") (pin "85") (pinfunction "PD14/FSMC_D0/TIM4_CH3/EVENTOUT_85") (pintype "bidirectional"))
    )
    (net (code "85") (name "unconnected-(U1B-PD15{slash}FSMC_D1{slash}TIM4_CH4{slash}EVENTOUT-Pad86)") (class "Default")
      (node (ref "U1") (pin "86") (pinfunction "PD15/FSMC_D1/TIM4_CH4/EVENTOUT_86") (pintype "bidirectional"))
    )
    (net (code "86") (name "unconnected-(U1C-PE0{slash}TIM4_ETR{slash}FSMC_NBL0{slash}DCMI_D2{slash}EVENTOUT-Pad141)") (class "Default")
      (node (ref "U1") (pin "141") (pinfunction "PE0/TIM4_ETR/FSMC_NBL0/DCMI_D2/EVENTOUT_141") (pintype "bidirectional"))
    )
    (net (code "87") (name "unconnected-(U1C-PE1{slash}FSMC_NBL1{slash}DCMI_D3{slash}EVENTOUT-Pad142)") (class "Default")
      (node (ref "U1") (pin "142") (pinfunction "PE1/FSMC_NBL1/DCMI_D3/EVENTOUT_142") (pintype "bidirectional"))
    )
    (net (code "88") (name "unconnected-(U1C-PE2{slash}TRACECLK{slash}FSMC_A23{slash}ETH_MII_TXD3{slash}EVENTOUT-Pad1)") (class "Default")
      (node (ref "U1") (pin "1") (pinfunction "PE2/TRACECLK/FSMC_A23/ETH_MII_TXD3/EVENTOUT_1") (pintype "bidirectional"))
    )
    (net (code "89") (name "unconnected-(U1C-PE3{slash}TRACED0{slash}FSMC_A19{slash}EVENTOUT-Pad2)") (class "Default")
      (node (ref "U1") (pin "2") (pinfunction "PE3/TRACED0/FSMC_A19/EVENTOUT_2") (pintype "bidirectional"))
    )
    (net (code "90") (name "unconnected-(U1C-PE4{slash}TRACED1{slash}FSMC_A20{slash}DCMI_D4{slash}EVENTOUT-Pad3)") (class "Default")
      (node (ref "U1") (pin "3") (pinfunction "PE4/TRACED1/FSMC_A20/DCMI_D4/EVENTOUT_3") (pintype "bidirectional"))
    )
    (net (code "91") (name "unconnected-(U1C-PE5{slash}TRACED2{slash}FSMC_A21{slash}TIM9_CH1{slash}DCMI_D6{slash}EVENTOUT-Pad4)") (class "Default")
      (node (ref "U1") (pin "4") (pinfunction "PE5/TRACED2/FSMC_A21/TIM9_CH1/DCMI_D6/EVENTOUT_4") (pintype "bidirectional"))
    )
    (net (code "92") (name "unconnected-(U1C-PE6{slash}TRACED3{slash}FSMC_A22{slash}TIM9_CH2{slash}DCMI_D7{slash}EVENTOUT-Pad5)") (class "Default")
      (node (ref "U1") (pin "5") (pinfunction "PE6/TRACED3/FSMC_A22/TIM9_CH2/DCMI_D7/EVENTOUT_5") (pintype "bidirectional"))
    )
    (net (code "93") (name "unconnected-(U1C-PE7{slash}FSMC_D4{slash}TIM1_ETR{slash}EVENTOUT-Pad58)") (class "Default")
      (node (ref "U1") (pin "58") (pinfunction "PE7/FSMC_D4/TIM1_ETR/EVENTOUT_58") (pintype "bidirectional"))
    )
    (net (code "94") (name "unconnected-(U1C-PE10{slash}FSMC_D7{slash}TIM1_CH2N{slash}EVENTOUT-Pad63)") (class "Default")
      (node (ref "U1") (pin "63") (pinfunction "PE10/FSMC_D7/TIM1_CH2N/EVENTOUT_63") (pintype "bidirectional"))
    )
    (net (code "95") (name "unconnected-(U1C-PE11{slash}FSMC_D8{slash}TIM1_CH2{slash}EVENTOUT-Pad64)") (class "Default")
      (node (ref "U1") (pin "64") (pinfunction "PE11/FSMC_D8/TIM1_CH2/EVENTOUT_64") (pintype "bidirectional"))
    )
    (net (code "96") (name "unconnected-(U1C-PE12{slash}FSMC_D9{slash}TIM1_CH3N{slash}EVENTOUT-Pad65)") (class "Default")
      (node (ref "U1") (pin "65") (pinfunction "PE12/FSMC_D9/TIM1_CH3N/EVENTOUT_65") (pintype "bidirectional"))
    )
    (net (code "97") (name "unconnected-(U1C-PE13{slash}FSMC_D10{slash}TIM1_CH3{slash}EVENTOUT-Pad66)") (class "Default")
      (node (ref "U1") (pin "66") (pinfunction "PE13/FSMC_D10/TIM1_CH3/EVENTOUT_66") (pintype "bidirectional"))
    )
    (net (code "98") (name "unconnected-(U1C-PE14{slash}FSMC_D11{slash}TIM1_CH4{slash}EVENTOUT-Pad67)") (class "Default")
      (node (ref "U1") (pin "67") (pinfunction "PE14/FSMC_D11/TIM1_CH4/EVENTOUT_67") (pintype "bidirectional"))
    )
    (net (code "99") (name "unconnected-(U1C-PE15{slash}FSMC_D12{slash}TIM1_BKIN{slash}EVENTOUT-Pad68)") (class "Default")
      (node (ref "U1") (pin "68") (pinfunction "PE15/FSMC_D12/TIM1_BKIN/EVENTOUT_68") (pintype "bidirectional"))
    )
    (net (code "100") (name "unconnected-(U1C-PF0{slash}FSMC_A0{slash}I2C2_SDA{slash}EVENTOUT-Pad10)") (class "Default")
      (node (ref "U1") (pin "10") (pinfunction "PF0/FSMC_A0/I2C2_SDA/EVENTOUT_10") (pintype "bidirectional"))
    )
    (net (code "101") (name "unconnected-(U1C-PF1{slash}FSMC_A1{slash}I2C2_SCL{slash}EVENTOUT-Pad11)") (class "Default")
      (node (ref "U1") (pin "11") (pinfunction "PF1/FSMC_A1/I2C2_SCL/EVENTOUT_11") (pintype "bidirectional"))
    )
    (net (code "102") (name "unconnected-(U1C-PF8{slash}TIM13_CH1{slash}FSMC_NIOWR{slash}EVENTOUT{slash}ADC3_IN6-Pad20)") (class "Default")
      (node (ref "U1") (pin "20") (pinfunction "PF8/TIM13_CH1/FSMC_NIOWR/EVENTOUT/ADC3_IN6_20") (pintype "bidirectional"))
    )
    (net (code "103") (name "unconnected-(U1C-PF9{slash}TIM14_CH1{slash}FSMC_CD{slash}EVENTOUT{slash}ADC3_IN7-Pad21)") (class "Default")
      (node (ref "U1") (pin "21") (pinfunction "PF9/TIM14_CH1/FSMC_CD/EVENTOUT/ADC3_IN7_21") (pintype "bidirectional"))
    )
    (net (code "104") (name "unconnected-(U1C-PF10{slash}FSMC_INTR{slash}EVENTOUT{slash}ADC3_IN8-Pad22)") (class "Default")
      (node (ref "U1") (pin "22") (pinfunction "PF10/FSMC_INTR/EVENTOUT/ADC3_IN8_22") (pintype "bidirectional"))
    )
    (net (code "105") (name "unconnected-(U1C-PF11{slash}DCMI_D12{slash}EVENTOUT-Pad49)") (class "Default")
      (node (ref "U1") (pin "49") (pinfunction "PF11/DCMI_D12/EVENTOUT_49") (pintype "bidirectional"))
    )
    (net (code "106") (name "unconnected-(U1C-PF12{slash}FSMC_A6{slash}EVENTOUT-Pad50)") (class "Default")
      (node (ref "U1") (pin "50") (pinfunction "PF12/FSMC_A6/EVENTOUT_50") (pintype "bidirectional"))
    )
    (net (code "107") (name "unconnected-(U1C-PF13{slash}FSMC_A7{slash}EVENTOUT-Pad53)") (class "Default")
      (node (ref "U1") (pin "53") (pinfunction "PF13/FSMC_A7/EVENTOUT_53") (pintype "bidirectional"))
    )
    (net (code "108") (name "unconnected-(U1C-PF14{slash}FSMC_A8{slash}EVENTOUT-Pad54)") (class "Default")
      (node (ref "U1") (pin "54") (pinfunction "PF14/FSMC_A8/EVENTOUT_54") (pintype "bidirectional"))
    )
    (net (code "109") (name "unconnected-(U1C-PF15{slash}FSMC_A9{slash}EVENTOUT-Pad55)") (class "Default")
      (node (ref "U1") (pin "55") (pinfunction "PF15/FSMC_A9/EVENTOUT_55") (pintype "bidirectional"))
    )
    (net (code "110") (name "unconnected-(U1D-PG0{slash}FSMC_A10{slash}EVENTOUT-Pad56)") (class "Default")
      (node (ref "U1") (pin "56") (pinfunction "PG0/FSMC_A10/EVENTOUT_56") (pintype "bidirectional"))
    )
    (net (code "111") (name "unconnected-(U1D-PG1{slash}FSMC_A11{slash}EVENTOUT-Pad57)") (class "Default")
      (node (ref "U1") (pin "57") (pinfunction "PG1/FSMC_A11/EVENTOUT_57") (pintype "bidirectional"))
    )
    (net (code "112") (name "unconnected-(U1D-PG2{slash}FSMC_A12{slash}EVENTOUT-Pad87)") (class "Default")
      (node (ref "U1") (pin "87") (pinfunction "PG2/FSMC_A12/EVENTOUT_87") (pintype "bidirectional"))
    )
    (net (code "113") (name "unconnected-(U1D-PG3{slash}FSMC_A13{slash}EVENTOUT-Pad88)") (class "Default")
      (node (ref "U1") (pin "88") (pinfunction "PG3/FSMC_A13/EVENTOUT_88") (pintype "bidirectional"))
    )
    (net (code "114") (name "unconnected-(U1D-PG4{slash}FSMC_A14{slash}EVENTOUT-Pad89)") (class "Default")
      (node (ref "U1") (pin "89") (pinfunction "PG4/FSMC_A14/EVENTOUT_89") (pintype "bidirectional"))
    )
    (net (code "115") (name "unconnected-(U1D-PG5{slash}FSMC_A15{slash}EVENTOUT-Pad90)") (class "Default")
      (node (ref "U1") (pin "90") (pinfunction "PG5/FSMC_A15/EVENTOUT_90") (pintype "bidirectional"))
    )
    (net (code "116") (name "unconnected-(U1D-PG6{slash}FSMC_INT2{slash}EVENTOUT-Pad91)") (class "Default")
      (node (ref "U1") (pin "91") (pinfunction "PG6/FSMC_INT2/EVENTOUT_91") (pintype "bidirectional"))
    )
    (net (code "117") (name "unconnected-(U1D-PG7{slash}FSMC_INT3{slash}USART6_CK{slash}EVENTOUT-Pad92)") (class "Default")
      (node (ref "U1") (pin "92") (pinfunction "PG7/FSMC_INT3/USART6_CK/EVENTOUT_92") (pintype "bidirectional"))
    )
    (net (code "118") (name "unconnected-(U1D-PG8{slash}USART6_RTS{slash}ETH_PPS_OUT{slash}EVENTOUT-Pad93)") (class "Default")
      (node (ref "U1") (pin "93") (pinfunction "PG8/USART6_RTS/ETH_PPS_OUT/EVENTOUT_93") (pintype "bidirectional"))
    )
    (net (code "119") (name "unconnected-(U1D-PG9{slash}USART6_RX{slash}FSMC_NE2{slash}FSMC_NCE3{slash}EVENTOUT-Pad124)") (class "Default")
      (node (ref "U1") (pin "124") (pinfunction "PG9/USART6_RX/FSMC_NE2/FSMC_NCE3/EVENTOUT_124") (pintype "bidirectional"))
    )
    (net (code "120") (name "unconnected-(U1D-PG10{slash}FSMC_NCE4_1{slash}FSMC_NE3{slash}EVENTOUT-Pad125)") (class "Default")
      (node (ref "U1") (pin "125") (pinfunction "PG10/FSMC_NCE4_1/FSMC_NE3/EVENTOUT_125") (pintype "bidirectional"))
    )
    (net (code "121") (name "unconnected-(U1D-PG11{slash}FSMC_NCE4_2{slash}ETH_MII_TX_EN{slash}ETH_RMII_TX_EN{slash}EVENTOUT-Pad126)") (class "Default")
      (node (ref "U1") (pin "126") (pinfunction "PG11/FSMC_NCE4_2/ETH_MII_TX_EN/ETH_RMII_TX_EN/EVENTOUT_126") (pintype "bidirectional"))
    )
    (net (code "122") (name "unconnected-(U1D-PG12{slash}FSMC_NE4{slash}USART6_RTS{slash}EVENTOUT-Pad127)") (class "Default")
      (node (ref "U1") (pin "127") (pinfunction "PG12/FSMC_NE4/USART6_RTS/EVENTOUT_127") (pintype "bidirectional"))
    )
    (net (code "123") (name "unconnected-(U1D-PG13{slash}FSMC_A24{slash}USART6_CTS{slash}ETH_MII_TXD0{slash}ETH_RMII_TXD0{slash}EVENTOUT-Pad128)") (class "Default")
      (node (ref "U1") (pin "128") (pinfunction "PG13/FSMC_A24/USART6_CTS/ETH_MII_TXD0/ETH_RMII_TXD0/EVENTOUT_128") (pintype "bidirectional"))
    )
    (net (code "124") (name "unconnected-(U1D-PG14{slash}FSMC_A25{slash}USART6_TX{slash}ETH_MII_TXD1{slash}ETH_RMII_TXD1{slash}EVENTOUT-Pad129)") (class "Default")
      (node (ref "U1") (pin "129") (pinfunction "PG14/FSMC_A25/USART6_TX/ETH_MII_TXD1/ETH_RMII_TXD1/EVENTOUT_129") (pintype "bidirectional"))
    )
    (net (code "125") (name "unconnected-(U1D-PG15{slash}USART6_CTS{slash}DCMI_D13{slash}EVENTOUT-Pad132)") (class "Default")
      (node (ref "U1") (pin "132") (pinfunction "PG15/USART6_CTS/DCMI_D13/EVENTOUT_132") (pintype "bidirectional"))
    )
    (net (code "126") (name "unconnected-(Y1-Pad2)") (class "Default")
      (node (ref "Y1") (pin "2") (pinfunction "2_2") (pintype "passive"))
    )
    (net (code "127") (name "unconnected-(Y1-Pad3)") (class "Default")
      (node (ref "Y1") (pin "3") (pinfunction "3_3") (pintype "passive"))
    )
  )
)
